# RecoveryBoard.net
KiCad netlist of a schematic drawn in EAGLE
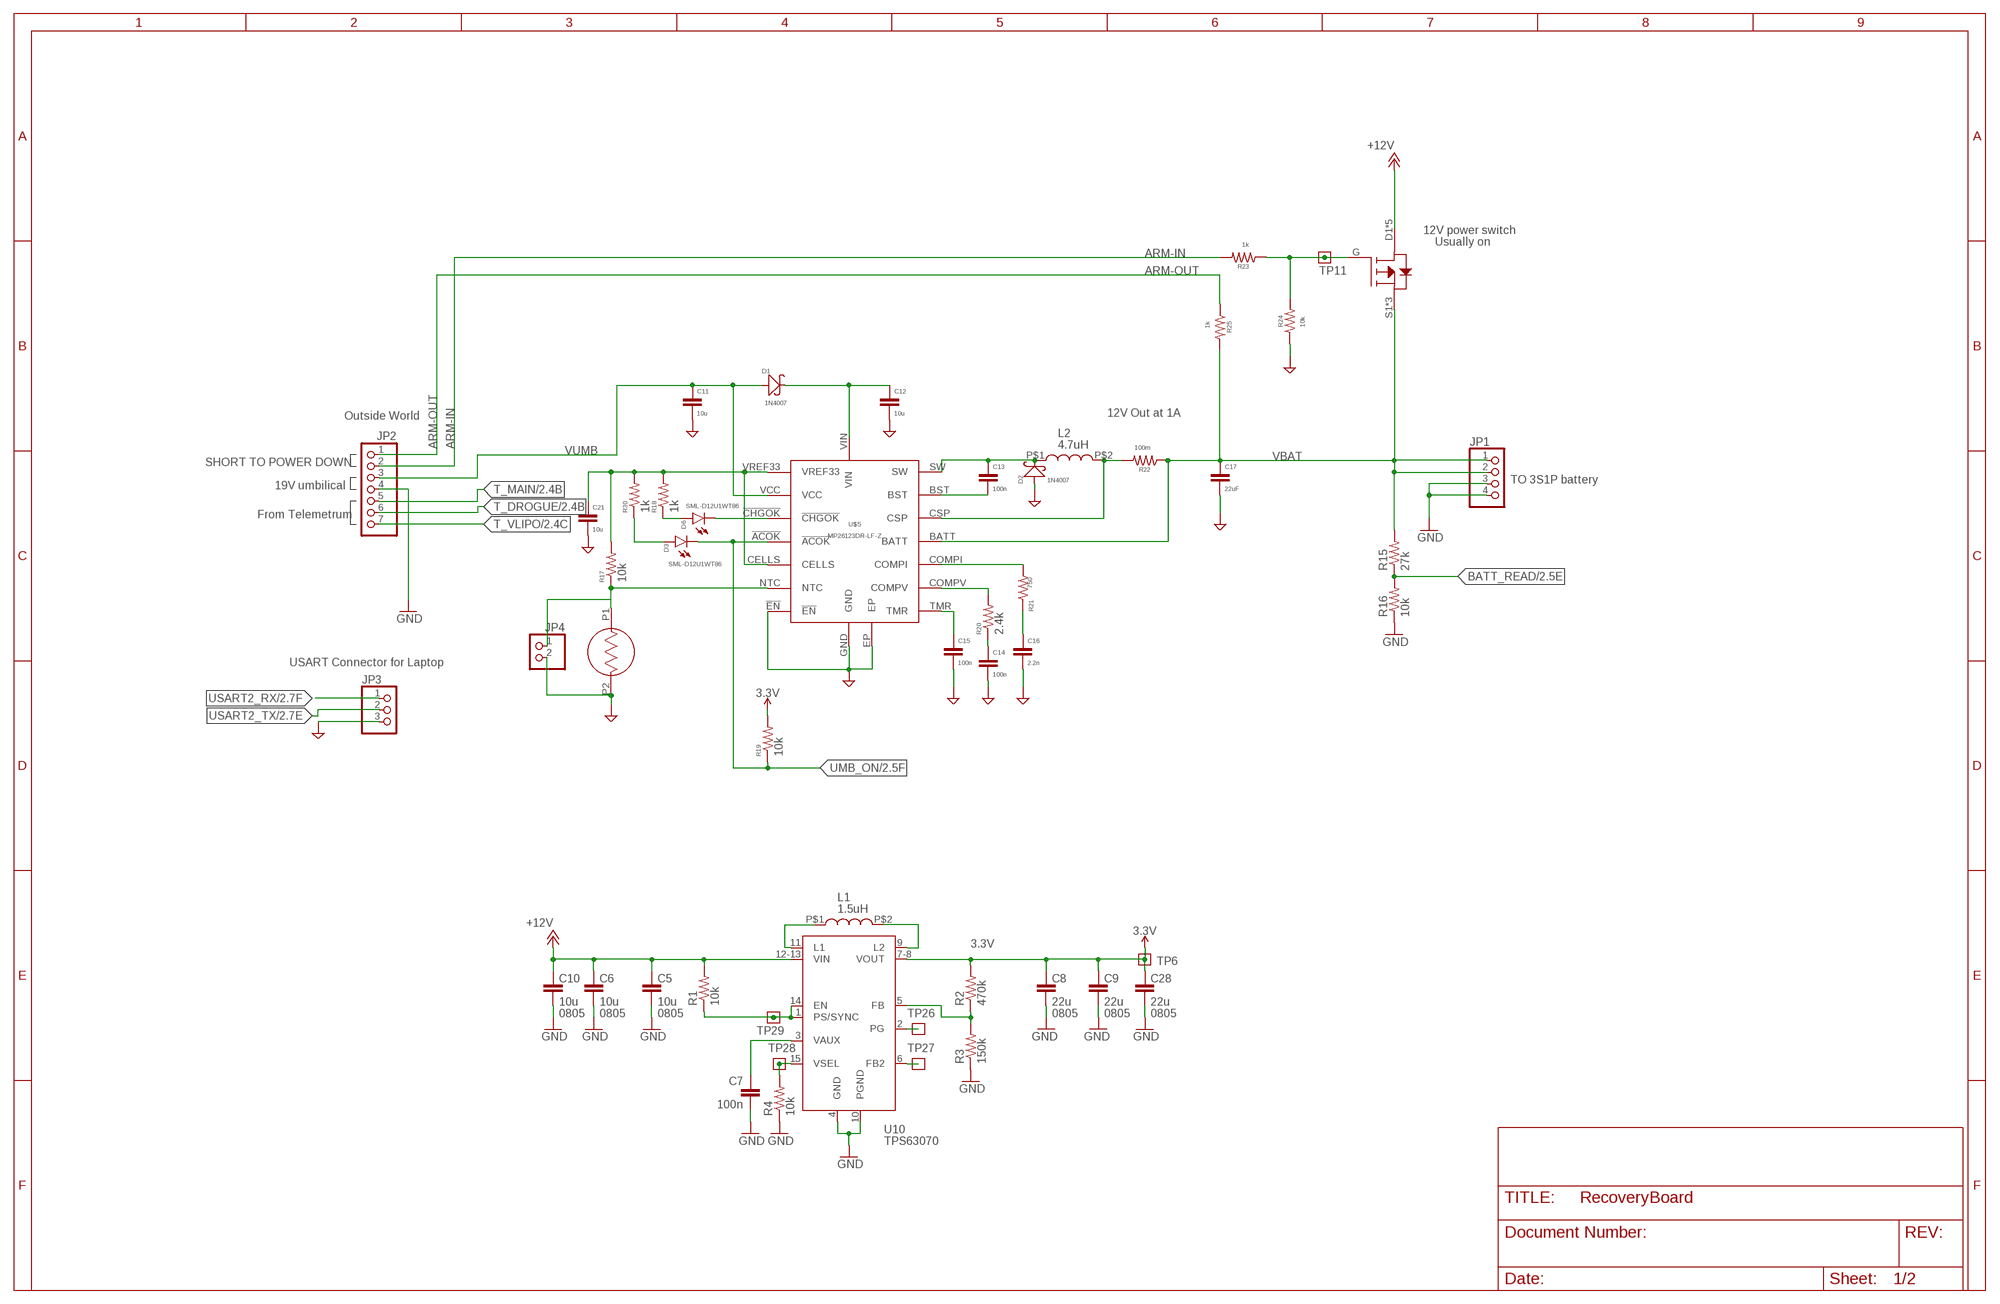
[diagram p0: schematic, sheet 1]
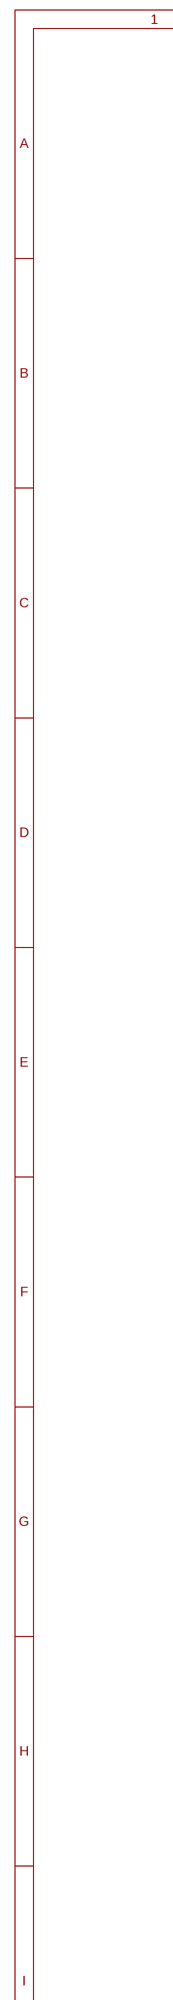
[diagram p1: schematic, sheet 2, part 1 of 2]
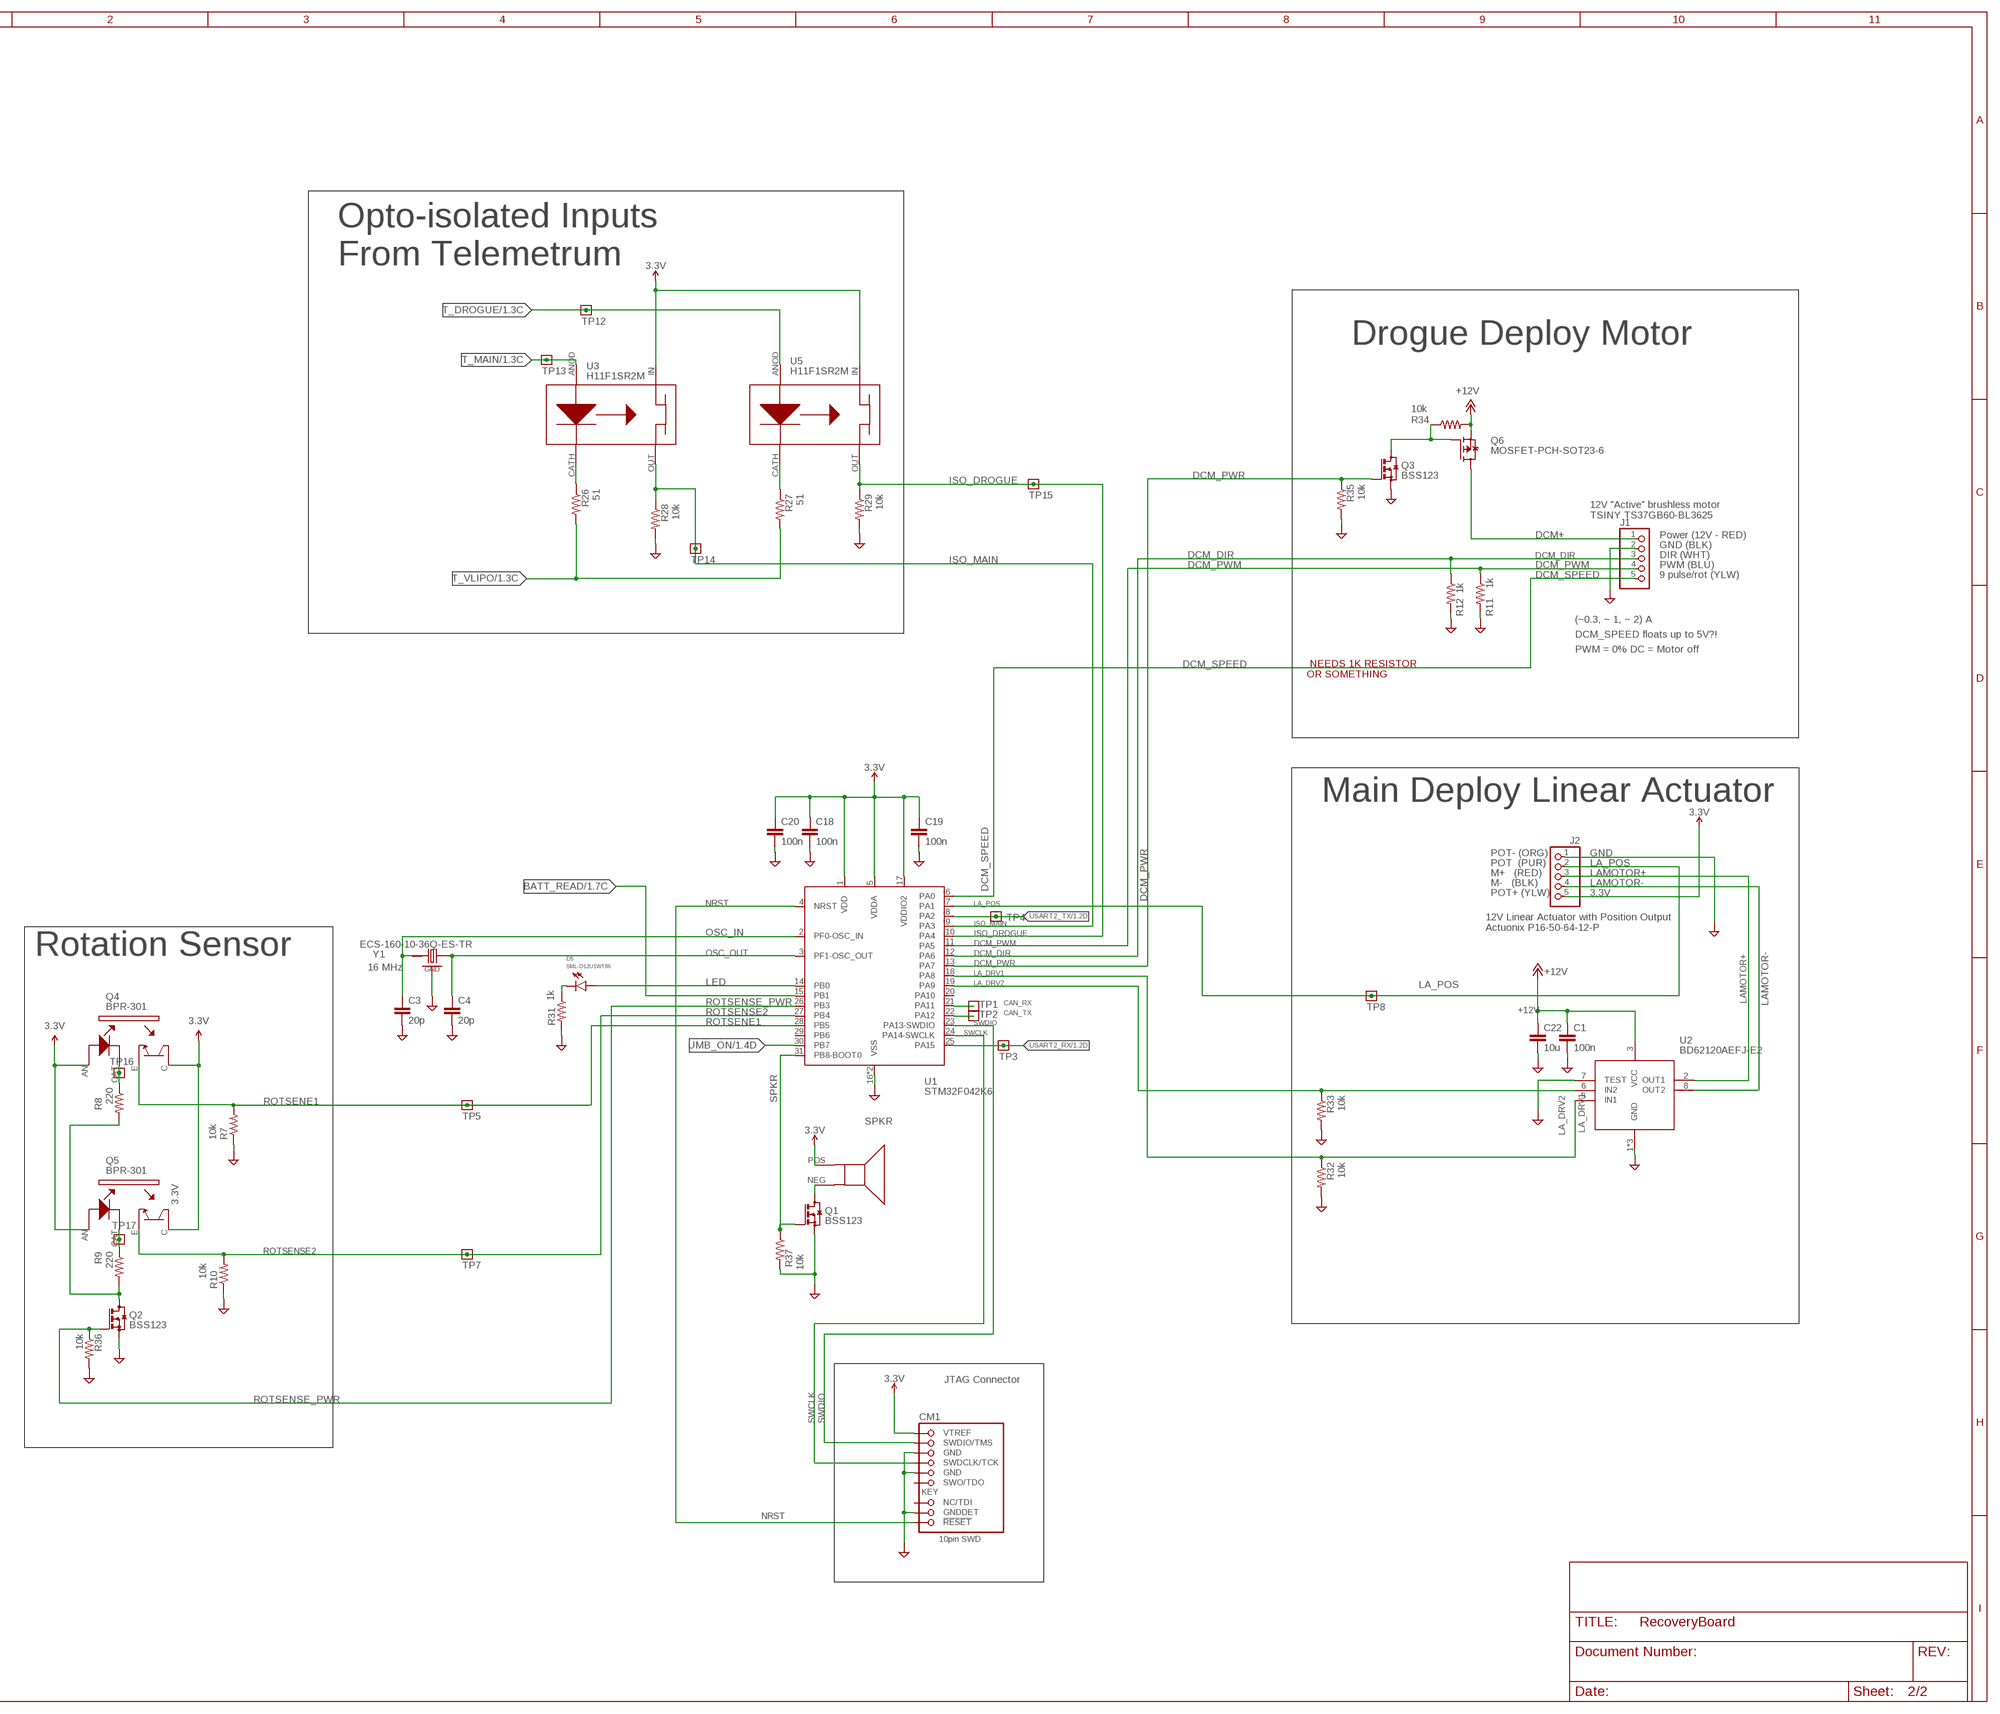
[diagram p2: schematic, sheet 2, part 2 of 2]

(export (version "E")
  (design (tool "Eeschema 10.0.6"))
  (components
    (comp (ref "C1")
      (value "100n")
      (footprint "eagle-import:.0603-C-NOSILK")
      (libsource (lib "eagle-import") (part "C-EU0603-C-NOSILK"))
    )
    (comp (ref "C3")
      (value "20p")
      (footprint "eagle-import:.0603-C-NOSILK")
      (libsource (lib "eagle-import") (part "C-EU0603-C-NOSILK"))
    )
    (comp (ref "C4")
      (value "20p")
      (footprint "eagle-import:.0603-C-NOSILK")
      (libsource (lib "eagle-import") (part "C-EU0603-C-NOSILK"))
    )
    (comp (ref "C18")
      (value "100n")
      (footprint "eagle-import:.0603-C-NOSILK")
      (libsource (lib "eagle-import") (part "C-EU0603-C-NOSILK"))
    )
    (comp (ref "C19")
      (value "100n")
      (footprint "eagle-import:.0603-C-NOSILK")
      (libsource (lib "eagle-import") (part "C-EU0603-C-NOSILK"))
    )
    (comp (ref "C20")
      (value "100n")
      (footprint "eagle-import:.0603-C-NOSILK")
      (libsource (lib "eagle-import") (part "C-EU0603-C-NOSILK"))
    )
    (comp (ref "C22")
      (value "10u")
      (footprint "eagle-import:.0805-A-NOSILK")
      (libsource (lib "eagle-import") (part "C-EU0805-A-NOSILK"))
    )
    (comp (ref "CM1")
      (value "FTSH-105-XX-X-DV-K")
      (footprint "eagle-import:CON10_2X5_DUK_FTSH")
      (libsource (lib "eagle-import") (part "FTSH-105-XX-X-DV-K"))
    )
    (comp (ref "D5")
      (value "SML-D12U1WT86")
      (footprint "eagle-import:CHIPLED_0603")
      (libsource (lib "eagle-import") (part "LEDCHIPLED_0603"))
    )
    (comp (ref "J1")
      (value "PINHD-1X5")
      (footprint "eagle-import:1X05")
      (libsource (lib "eagle-import") (part "PINHD-1X5"))
    )
    (comp (ref "J2")
      (value "PINHD-1X5")
      (footprint "eagle-import:1X05")
      (libsource (lib "eagle-import") (part "PINHD-1X5"))
    )
    (comp (ref "Q1")
      (value "BSS123")
      (footprint "eagle-import:SOT23")
      (libsource (lib "eagle-import") (part "BSS123"))
    )
    (comp (ref "Q2")
      (value "BSS123")
      (footprint "eagle-import:SOT23")
      (libsource (lib "eagle-import") (part "BSS123"))
    )
    (comp (ref "Q3")
      (value "BSS123")
      (footprint "eagle-import:SOT23")
      (libsource (lib "eagle-import") (part "BSS123"))
    )
    (comp (ref "Q4")
      (value "BPR-301")
      (footprint "eagle-import:BPR-301")
      (libsource (lib "eagle-import") (part "BPR-301"))
    )
    (comp (ref "Q5")
      (value "BPR-301")
      (footprint "eagle-import:BPR-301")
      (libsource (lib "eagle-import") (part "BPR-301"))
    )
    (comp (ref "Q6")
      (value "MOSFET-PCH-SOT23-6")
      (footprint "eagle-import:SOT23-6")
      (libsource (lib "eagle-import") (part "MOSFET-PCH-SOT23-6"))
    )
    (comp (ref "R7")
      (value "10k")
      (footprint "eagle-import:.0603-C-NOSILK")
      (libsource (lib "eagle-import") (part "R-US_0603-C-NOSILK"))
    )
    (comp (ref "R8")
      (value "220")
      (footprint "eagle-import:.0603-C-NOSILK")
      (libsource (lib "eagle-import") (part "R-US_0603-C-NOSILK"))
    )
    (comp (ref "R9")
      (value "220")
      (footprint "eagle-import:.0603-C-NOSILK")
      (libsource (lib "eagle-import") (part "R-US_0603-C-NOSILK"))
    )
    (comp (ref "R10")
      (value "10k")
      (footprint "eagle-import:.0603-C-NOSILK")
      (libsource (lib "eagle-import") (part "R-US_0603-C-NOSILK"))
    )
    (comp (ref "R11")
      (value "1k")
      (footprint "eagle-import:.0603-C-NOSILK")
      (libsource (lib "eagle-import") (part "R-US_0603-C-NOSILK"))
    )
    (comp (ref "R12")
      (value "1k")
      (footprint "eagle-import:.0603-C-NOSILK")
      (libsource (lib "eagle-import") (part "R-US_0603-C-NOSILK"))
    )
    (comp (ref "R26")
      (value "51")
      (footprint "eagle-import:.0603-C-NOSILK")
      (libsource (lib "eagle-import") (part "R-US_0603-C-NOSILK"))
    )
    (comp (ref "R27")
      (value "51")
      (footprint "eagle-import:.0603-C-NOSILK")
      (libsource (lib "eagle-import") (part "R-US_0603-C-NOSILK"))
    )
    (comp (ref "R28")
      (value "10k")
      (footprint "eagle-import:.0603-C-NOSILK")
      (libsource (lib "eagle-import") (part "R-US_0603-C-NOSILK"))
    )
    (comp (ref "R29")
      (value "10k")
      (footprint "eagle-import:.0603-C-NOSILK")
      (libsource (lib "eagle-import") (part "R-US_0603-C-NOSILK"))
    )
    (comp (ref "R31")
      (value "1k")
      (footprint "eagle-import:.0603-C-NOSILK")
      (libsource (lib "eagle-import") (part "R-US_0603-C-NOSILK"))
    )
    (comp (ref "R32")
      (value "10k")
      (footprint "eagle-import:.0603-C-NOSILK")
      (libsource (lib "eagle-import") (part "R-US_0603-C-NOSILK"))
    )
    (comp (ref "R33")
      (value "10k")
      (footprint "eagle-import:.0603-C-NOSILK")
      (libsource (lib "eagle-import") (part "R-US_0603-C-NOSILK"))
    )
    (comp (ref "R34")
      (value "10k")
      (footprint "eagle-import:.0603-C-NOSILK")
      (libsource (lib "eagle-import") (part "R-US_0603-C-NOSILK"))
    )
    (comp (ref "R35")
      (value "10k")
      (footprint "eagle-import:.0603-C-NOSILK")
      (libsource (lib "eagle-import") (part "R-US_0603-C-NOSILK"))
    )
    (comp (ref "R36")
      (value "10k")
      (footprint "eagle-import:.0603-C-NOSILK")
      (libsource (lib "eagle-import") (part "R-US_0603-C-NOSILK"))
    )
    (comp (ref "R37")
      (value "10k")
      (footprint "eagle-import:.0603-C-NOSILK")
      (libsource (lib "eagle-import") (part "R-US_0603-C-NOSILK"))
    )
    (comp (ref "TP1")
      (value "TEST-POINT")
      (footprint "eagle-import:2MM-TEST-POINT")
      (libsource (lib "eagle-import") (part "TEST-POINT"))
    )
    (comp (ref "TP2")
      (value "TEST-POINT")
      (footprint "eagle-import:2MM-TEST-POINT")
      (libsource (lib "eagle-import") (part "TEST-POINT"))
    )
    (comp (ref "TP3")
      (value "TEST-POINT")
      (footprint "eagle-import:2MM-TEST-POINT")
      (libsource (lib "eagle-import") (part "TEST-POINT"))
    )
    (comp (ref "TP4")
      (value "TEST-POINT")
      (footprint "eagle-import:2MM-TEST-POINT")
      (libsource (lib "eagle-import") (part "TEST-POINT"))
    )
    (comp (ref "TP5")
      (value "TEST-POINT")
      (footprint "eagle-import:2MM-TEST-POINT")
      (libsource (lib "eagle-import") (part "TEST-POINT"))
    )
    (comp (ref "TP7")
      (value "TEST-POINT")
      (footprint "eagle-import:2MM-TEST-POINT")
      (libsource (lib "eagle-import") (part "TEST-POINT"))
    )
    (comp (ref "TP8")
      (value "TEST-POINT")
      (footprint "eagle-import:2MM-TEST-POINT")
      (libsource (lib "eagle-import") (part "TEST-POINT"))
    )
    (comp (ref "TP12")
      (value "TEST-POINT")
      (footprint "eagle-import:2MM-TEST-POINT")
      (libsource (lib "eagle-import") (part "TEST-POINT"))
    )
    (comp (ref "TP13")
      (value "TEST-POINT")
      (footprint "eagle-import:2MM-TEST-POINT")
      (libsource (lib "eagle-import") (part "TEST-POINT"))
    )
    (comp (ref "TP14")
      (value "TEST-POINT")
      (footprint "eagle-import:2MM-TEST-POINT")
      (libsource (lib "eagle-import") (part "TEST-POINT"))
    )
    (comp (ref "TP15")
      (value "TEST-POINT")
      (footprint "eagle-import:2MM-TEST-POINT")
      (libsource (lib "eagle-import") (part "TEST-POINT"))
    )
    (comp (ref "TP16")
      (value "TEST-POINT")
      (footprint "eagle-import:2MM-TEST-POINT")
      (libsource (lib "eagle-import") (part "TEST-POINT"))
    )
    (comp (ref "TP17")
      (value "TEST-POINT")
      (footprint "eagle-import:2MM-TEST-POINT")
      (libsource (lib "eagle-import") (part "TEST-POINT"))
    )
    (comp (ref "U$7")
      (value "SMT-0440-S-R")
      (footprint "eagle-import:SMT-0440-S-R")
      (libsource (lib "eagle-import") (part "SMT-0440-S-R"))
    )
    (comp (ref "U1")
      (value "STM32F042K6")
      (footprint "eagle-import:QFP32-7X7")
      (libsource (lib "eagle-import") (part "STM32F042K6"))
    )
    (comp (ref "U2")
      (value "BD62120AEFJ-E2")
      (footprint "eagle-import:SOIC127P600X100-9N")
      (fields (field (name "MOUSER_PART_NUMBER") "755-BD62120AEFJ-E2"))
      (libsource (lib "eagle-import") (part "BD62120AEFJ-E2"))
    )
    (comp (ref "U3")
      (value "H11F1SR2M")
      (footprint "eagle-import:H11F1SR2M")
      (libsource (lib "eagle-import") (part "H11F1SR2M"))
    )
    (comp (ref "U5")
      (value "H11F1SR2M")
      (footprint "eagle-import:H11F1SR2M")
      (libsource (lib "eagle-import") (part "H11F1SR2M"))
    )
    (comp (ref "Y1")
      (value "ECS-160-10-36Q-ES-TR")
      (footprint "eagle-import:XTAL_ECS-160-10-36Q-ES-TR")
      (fields (field (name "DIGI-KEY_PART_NUMBER") "XC2181CT-ND") (field (name "MF") "ECS Inc."))
      (libsource (lib "eagle-import") (part "ECS-160-10-36Q-ES-TR"))
    )
    (comp (ref "C5")
      (value "10u")
      (footprint "eagle-import:.0805-C-NOSILK")
      (fields (field (name "MFR") "Samsung") (field (name "MPN") "CL05B104KO5NNNC"))
      (libsource (lib "eagle-import") (part "C-EU0805-C-NOSILK"))
    )
    (comp (ref "C6")
      (value "10u")
      (footprint "eagle-import:.0805-C-NOSILK")
      (libsource (lib "eagle-import") (part "C-EU0805-C-NOSILK"))
    )
    (comp (ref "C7")
      (value "100n")
      (footprint "eagle-import:.0603-C-NOSILK")
      (fields (field (name "MFR") "Samsung") (field (name "MPN") "CL05B104KO5NNNC"))
      (libsource (lib "eagle-import") (part "C-EU0603-C-NOSILK"))
    )
    (comp (ref "C8")
      (value "22u")
      (footprint "eagle-import:.0805-C-NOSILK")
      (fields (field (name "MFR") "Samsung") (field (name "MPN") "CL05B104KO5NNNC"))
      (libsource (lib "eagle-import") (part "C-EU0805-C-NOSILK"))
    )
    (comp (ref "C9")
      (value "22u")
      (footprint "eagle-import:.0805-C-NOSILK")
      (libsource (lib "eagle-import") (part "C-EU0805-C-NOSILK"))
    )
    (comp (ref "C10")
      (value "10u")
      (footprint "eagle-import:.0805-C-NOSILK")
      (libsource (lib "eagle-import") (part "C-EU0805-C-NOSILK"))
    )
    (comp (ref "C11")
      (value "10u")
      (footprint "eagle-import:.0805-C-NOSILK")
      (libsource (lib "eagle-import") (part "C-EU0805-C-NOSILK"))
    )
    (comp (ref "C12")
      (value "10u")
      (footprint "eagle-import:.0805-C-NOSILK")
      (libsource (lib "eagle-import") (part "C-EU0805-C-NOSILK"))
    )
    (comp (ref "C13")
      (value "100n")
      (footprint "eagle-import:.0603-C-NOSILK")
      (libsource (lib "eagle-import") (part "C-EU0603-C-NOSILK"))
    )
    (comp (ref "C14")
      (value "100n")
      (footprint "eagle-import:.0603-C-NOSILK")
      (libsource (lib "eagle-import") (part "C-EU0603-C-NOSILK"))
    )
    (comp (ref "C15")
      (value "100n")
      (footprint "eagle-import:.0603-C-NOSILK")
      (libsource (lib "eagle-import") (part "C-EU0603-C-NOSILK"))
    )
    (comp (ref "C16")
      (value "2.2n")
      (footprint "eagle-import:.0603-C-NOSILK")
      (libsource (lib "eagle-import") (part "C-EU0603-C-NOSILK"))
    )
    (comp (ref "C17")
      (value "22uF")
      (footprint "eagle-import:.0805-C-NOSILK")
      (libsource (lib "eagle-import") (part "C-EU0805-C-NOSILK"))
    )
    (comp (ref "C21")
      (value "10u")
      (footprint "eagle-import:.0805-C-NOSILK")
      (libsource (lib "eagle-import") (part "C-EU0805-C-NOSILK"))
    )
    (comp (ref "C28")
      (value "22u")
      (footprint "eagle-import:.0805-C-NOSILK")
      (libsource (lib "eagle-import") (part "C-EU0805-C-NOSILK"))
    )
    (comp (ref "D1")
      (value "1N4007")
      (footprint "eagle-import:DO-214AC")
      (libsource (lib "eagle-import") (part "DIODE-SCHOTTKY-(DO-214AC)"))
    )
    (comp (ref "D2")
      (value "1N4007")
      (footprint "eagle-import:DO-214AC")
      (libsource (lib "eagle-import") (part "DIODE-SCHOTTKY-(DO-214AC)"))
    )
    (comp (ref "D3")
      (value "SML-D12U1WT86")
      (footprint "eagle-import:CHIPLED_0603")
      (libsource (lib "eagle-import") (part "LEDCHIPLED_0603"))
    )
    (comp (ref "D6")
      (value "SML-D12U1WT86")
      (footprint "eagle-import:CHIPLED_0603")
      (libsource (lib "eagle-import") (part "LEDCHIPLED_0603"))
    )
    (comp (ref "JP1")
      (value "PINHD-1X4")
      (footprint "eagle-import:1X04")
      (libsource (lib "eagle-import") (part "PINHD-1X4"))
    )
    (comp (ref "JP2")
      (value "PINHD-1X7")
      (footprint "eagle-import:1X07")
      (libsource (lib "eagle-import") (part "PINHD-1X7"))
    )
    (comp (ref "JP3")
      (value "PINHD-1X3")
      (footprint "eagle-import:1X03")
      (libsource (lib "eagle-import") (part "PINHD-1X3"))
    )
    (comp (ref "JP4")
      (value "PINHD-1X2")
      (footprint "eagle-import:1X02")
      (libsource (lib "eagle-import") (part "PINHD-1X2"))
    )
    (comp (ref "L1")
      (value "1.5uH")
      (footprint "eagle-import:IHLP2020CZER1R5M11")
      (fields (field (name "MFR") "Vishay Dale") (field (name "MPN") "IHLP2020BZER4R7M11"))
      (libsource (lib "eagle-import") (part "IHLP2020CZER1R5M11"))
    )
    (comp (ref "L2")
      (value "4.7uH")
      (footprint "eagle-import:IHLP2020BZER4R7M11")
      (fields (field (name "MFR") "Vishay Dale") (field (name "MPN") "IHLP2020BZER4R7M11"))
      (libsource (lib "eagle-import") (part "IHLP2020BZER4R7M11"))
    )
    (comp (ref "Q7")
      (value "SI7465DP-T1-E3")
      (footprint "eagle-import:SI7465DP-T1-E3CT-ND")
      (fields (field (name "MFR") "Vishay Siliconix"))
      (libsource (lib "eagle-import") (part "SI7465DP-T1-E3"))
    )
    (comp (ref "R1")
      (value "10k")
      (footprint "eagle-import:.0603-C-NOSILK")
      (fields (field (name "MFR") "Samsung") (field (name "MPN") "RC1005F6653CS"))
      (libsource (lib "eagle-import") (part "R-US_0603-C-NOSILK"))
    )
    (comp (ref "R2")
      (value "470k")
      (footprint "eagle-import:.0603-C-NOSILK")
      (fields (field (name "MFR") "Samsung") (field (name "MPN") "RC1005F6653CS"))
      (libsource (lib "eagle-import") (part "R-US_0603-C-NOSILK"))
    )
    (comp (ref "R3")
      (value "150k")
      (footprint "eagle-import:.0603-C-NOSILK")
      (fields (field (name "MFR") "Samsung") (field (name "MPN") "RC1005F6653CS"))
      (libsource (lib "eagle-import") (part "R-US_0603-C-NOSILK"))
    )
    (comp (ref "R4")
      (value "10k")
      (footprint "eagle-import:.0603-C-NOSILK")
      (fields (field (name "MFR") "Samsung") (field (name "MPN") "RC1005F6653CS"))
      (libsource (lib "eagle-import") (part "R-US_0603-C-NOSILK"))
    )
    (comp (ref "R5")
      (value "NHQ103B375T10")
      (footprint "eagle-import:NHQ103B375T10")
      (libsource (lib "eagle-import") (part "NHQ103B375T10"))
    )
    (comp (ref "R15")
      (value "27k")
      (footprint "eagle-import:.0603-C-NOSILK")
      (fields (field (name "MFR") "Samsung") (field (name "MPN") "RC1005F6653CS"))
      (libsource (lib "eagle-import") (part "R-US_0603-C-NOSILK"))
    )
    (comp (ref "R16")
      (value "10k")
      (footprint "eagle-import:.0603-C-NOSILK")
      (fields (field (name "MFR") "Samsung") (field (name "MPN") "RC1005F6653CS"))
      (libsource (lib "eagle-import") (part "R-US_0603-C-NOSILK"))
    )
    (comp (ref "R17")
      (value "10k")
      (footprint "eagle-import:.0603-C-NOSILK")
      (libsource (lib "eagle-import") (part "R-US_0603-C-NOSILK"))
    )
    (comp (ref "R18")
      (value "1k")
      (footprint "eagle-import:.0603-C-NOSILK")
      (libsource (lib "eagle-import") (part "R-US_0603-C-NOSILK"))
    )
    (comp (ref "R19")
      (value "10k")
      (footprint "eagle-import:.0603-C-NOSILK")
      (libsource (lib "eagle-import") (part "R-US_0603-C-NOSILK"))
    )
    (comp (ref "R20")
      (value "2.4k")
      (footprint "eagle-import:.0603-C-NOSILK")
      (libsource (lib "eagle-import") (part "R-US_0603-C-NOSILK"))
    )
    (comp (ref "R21")
      (value "750")
      (footprint "eagle-import:.0603-C-NOSILK")
      (libsource (lib "eagle-import") (part "R-US_0603-C-NOSILK"))
    )
    (comp (ref "R22")
      (value "100m")
      (footprint "eagle-import:1206-C")
      (libsource (lib "eagle-import") (part "R-US_1206-C"))
    )
    (comp (ref "R23")
      (value "1k")
      (footprint "eagle-import:.0603-C-NOSILK")
      (libsource (lib "eagle-import") (part "R-US_0603-C-NOSILK"))
    )
    (comp (ref "R24")
      (value "10k")
      (footprint "eagle-import:.0603-C-NOSILK")
      (libsource (lib "eagle-import") (part "R-US_0603-C-NOSILK"))
    )
    (comp (ref "R25")
      (value "1k")
      (footprint "eagle-import:.0603-C-NOSILK")
      (libsource (lib "eagle-import") (part "R-US_0603-C-NOSILK"))
    )
    (comp (ref "R30")
      (value "1k")
      (footprint "eagle-import:.0603-C-NOSILK")
      (libsource (lib "eagle-import") (part "R-US_0603-C-NOSILK"))
    )
    (comp (ref "TP6")
      (value "TEST-POINT")
      (footprint "eagle-import:2MM-TEST-POINT")
      (libsource (lib "eagle-import") (part "TEST-POINT"))
    )
    (comp (ref "TP11")
      (value "TEST-POINT")
      (footprint "eagle-import:2MM-TEST-POINT")
      (libsource (lib "eagle-import") (part "TEST-POINT"))
    )
    (comp (ref "TP26")
      (value "TEST-POINT")
      (footprint "eagle-import:2MM-TEST-POINT")
      (libsource (lib "eagle-import") (part "TEST-POINT"))
    )
    (comp (ref "TP27")
      (value "TEST-POINT")
      (footprint "eagle-import:2MM-TEST-POINT")
      (libsource (lib "eagle-import") (part "TEST-POINT"))
    )
    (comp (ref "TP28")
      (value "TEST-POINT")
      (footprint "eagle-import:2MM-TEST-POINT")
      (libsource (lib "eagle-import") (part "TEST-POINT"))
    )
    (comp (ref "TP29")
      (value "TEST-POINT")
      (footprint "eagle-import:2MM-TEST-POINT")
      (libsource (lib "eagle-import") (part "TEST-POINT"))
    )
    (comp (ref "U$5")
      (value "MP26123DR-LF-Z")
      (footprint "eagle-import:MP26123DR-LF-Z")
      (libsource (lib "eagle-import") (part "MP26123DR-LF-Z"))
    )
    (comp (ref "U10")
      (value "TPS63070")
      (footprint "eagle-import:TPS63070X")
      (libsource (lib "eagle-import") (part "TPS63070X"))
    )
  )
  (nets
    (net (code "1") (name "+12V") (class "Default")
      (node (ref "C1") (pin "1") (pinfunction "1_1") (pintype "passive"))
      (node (ref "C10") (pin "1") (pinfunction "1_1") (pintype "passive"))
      (node (ref "C22") (pin "1") (pinfunction "1_1") (pintype "passive"))
      (node (ref "C5") (pin "1") (pinfunction "1_1") (pintype "passive"))
      (node (ref "C6") (pin "1") (pinfunction "1_1") (pintype "passive"))
      (node (ref "Q6") (pin "4") (pinfunction "S_4") (pintype "passive"))
      (node (ref "Q7") (pin "D1") (pinfunction "D_D1") (pintype "bidirectional"))
      (node (ref "Q7") (pin "D2") (pinfunction "D_D2") (pintype "bidirectional"))
      (node (ref "Q7") (pin "D3") (pinfunction "D_D3") (pintype "bidirectional"))
      (node (ref "Q7") (pin "D4") (pinfunction "D_D4") (pintype "bidirectional"))
      (node (ref "Q7") (pin "DPAD") (pinfunction "D_DPAD") (pintype "bidirectional"))
      (node (ref "R1") (pin "2") (pinfunction "2_2") (pintype "passive"))
      (node (ref "R34") (pin "2") (pinfunction "2_2") (pintype "passive"))
      (node (ref "U10") (pin "12-13") (pinfunction "VIN_12-13") (pintype "power_in"))
      (node (ref "U2") (pin "3") (pinfunction "VCC_3") (pintype "bidirectional"))
    )
    (net (code "2") (name "3.3V") (class "Default")
      (node (ref "C18") (pin "1") (pinfunction "1_1") (pintype "passive"))
      (node (ref "C19") (pin "1") (pinfunction "1_1") (pintype "passive"))
      (node (ref "C20") (pin "1") (pinfunction "1_1") (pintype "passive"))
      (node (ref "C28") (pin "1") (pinfunction "1_1") (pintype "passive"))
      (node (ref "C8") (pin "1") (pinfunction "1_1") (pintype "passive"))
      (node (ref "C9") (pin "1") (pinfunction "1_1") (pintype "passive"))
      (node (ref "CM1") (pin "1") (pinfunction "VTREF_1") (pintype "passive"))
      (node (ref "J2") (pin "5") (pinfunction "5_5") (pintype "passive"))
      (node (ref "Q4") (pin "AN") (pinfunction "ANOD_AN") (pintype "bidirectional"))
      (node (ref "Q4") (pin "C") (pinfunction "COLL_C") (pintype "bidirectional"))
      (node (ref "Q5") (pin "AN") (pinfunction "ANOD_AN") (pintype "bidirectional"))
      (node (ref "Q5") (pin "C") (pinfunction "COLL_C") (pintype "bidirectional"))
      (node (ref "R19") (pin "2") (pinfunction "2_2") (pintype "passive"))
      (node (ref "R2") (pin "2") (pinfunction "2_2") (pintype "passive"))
      (node (ref "TP6") (pin "1") (pinfunction "1_1") (pintype "passive"))
      (node (ref "U$7") (pin "POS") (pinfunction "POS_POS") (pintype "bidirectional"))
      (node (ref "U1") (pin "1") (pinfunction "VDD_1") (pintype "power_in"))
      (node (ref "U1") (pin "17") (pinfunction "VDDIO2_17") (pintype "power_in"))
      (node (ref "U1") (pin "5") (pinfunction "VDDA_5") (pintype "power_in"))
      (node (ref "U10") (pin "7-8") (pinfunction "VOUT_7-8") (pintype "power_in"))
      (node (ref "U3") (pin "IN") (pinfunction "IN_IN") (pintype "bidirectional"))
      (node (ref "U5") (pin "IN") (pinfunction "IN_IN") (pintype "bidirectional"))
    )
    (net (code "3") (name "ARM-IN") (class "Default")
      (node (ref "JP2") (pin "2") (pinfunction "2_2") (pintype "passive"))
      (node (ref "R23") (pin "2") (pinfunction "2_2") (pintype "passive"))
    )
    (net (code "4") (name "ARM-OUT") (class "Default")
      (node (ref "JP2") (pin "1") (pinfunction "1_1") (pintype "passive"))
      (node (ref "R25") (pin "1") (pinfunction "1_1") (pintype "passive"))
    )
    (net (code "5") (name "BATT_READ") (class "Default")
      (node (ref "R15") (pin "1") (pinfunction "1_1") (pintype "passive"))
      (node (ref "R16") (pin "2") (pinfunction "2_2") (pintype "passive"))
      (node (ref "U1") (pin "15") (pinfunction "PB1_15") (pintype "bidirectional"))
    )
    (net (code "6") (name "CAN_RX") (class "Default")
      (node (ref "TP1") (pin "1") (pinfunction "1_1") (pintype "passive"))
      (node (ref "U1") (pin "21") (pinfunction "PA11_21") (pintype "bidirectional"))
    )
    (net (code "7") (name "CAN_TX") (class "Default")
      (node (ref "TP2") (pin "1") (pinfunction "1_1") (pintype "passive"))
      (node (ref "U1") (pin "22") (pinfunction "PA12_22") (pintype "bidirectional"))
    )
    (net (code "8") (name "DCM+") (class "Default")
      (node (ref "J1") (pin "1") (pinfunction "1_1") (pintype "passive"))
      (node (ref "Q6") (pin "1") (pinfunction "D_1") (pintype "passive"))
      (node (ref "Q6") (pin "2") (pinfunction "D_2") (pintype "passive"))
      (node (ref "Q6") (pin "5") (pinfunction "D_5") (pintype "passive"))
      (node (ref "Q6") (pin "6") (pinfunction "D_6") (pintype "passive"))
    )
    (net (code "9") (name "DCM_DIR") (class "Default")
      (node (ref "J1") (pin "3") (pinfunction "3_3") (pintype "passive"))
      (node (ref "R12") (pin "1") (pinfunction "1_1") (pintype "passive"))
      (node (ref "U1") (pin "12") (pinfunction "PA6_12") (pintype "bidirectional"))
    )
    (net (code "10") (name "DCM_PWM") (class "Default")
      (node (ref "J1") (pin "4") (pinfunction "4_4") (pintype "passive"))
      (node (ref "R11") (pin "1") (pinfunction "1_1") (pintype "passive"))
      (node (ref "U1") (pin "11") (pinfunction "PA5_11") (pintype "bidirectional"))
    )
    (net (code "11") (name "DCM_PWR") (class "Default")
      (node (ref "Q3") (pin "1") (pinfunction "G_1") (pintype "passive"))
      (node (ref "R35") (pin "1") (pinfunction "1_1") (pintype "passive"))
      (node (ref "U1") (pin "13") (pinfunction "PA7_13") (pintype "bidirectional"))
    )
    (net (code "12") (name "DCM_SPEED") (class "Default")
      (node (ref "J1") (pin "5") (pinfunction "5_5") (pintype "passive"))
      (node (ref "U1") (pin "6") (pinfunction "PA0_6") (pintype "bidirectional"))
    )
    (net (code "13") (name "GND") (class "Default")
      (node (ref "C1") (pin "2") (pinfunction "2_2") (pintype "passive"))
      (node (ref "C10") (pin "2") (pinfunction "2_2") (pintype "passive"))
      (node (ref "C11") (pin "2") (pinfunction "2_2") (pintype "passive"))
      (node (ref "C12") (pin "2") (pinfunction "2_2") (pintype "passive"))
      (node (ref "C14") (pin "2") (pinfunction "2_2") (pintype "passive"))
      (node (ref "C15") (pin "2") (pinfunction "2_2") (pintype "passive"))
      (node (ref "C16") (pin "2") (pinfunction "2_2") (pintype "passive"))
      (node (ref "C17") (pin "2") (pinfunction "2_2") (pintype "passive"))
      (node (ref "C18") (pin "2") (pinfunction "2_2") (pintype "passive"))
      (node (ref "C19") (pin "2") (pinfunction "2_2") (pintype "passive"))
      (node (ref "C20") (pin "2") (pinfunction "2_2") (pintype "passive"))
      (node (ref "C21") (pin "2") (pinfunction "2_2") (pintype "passive"))
      (node (ref "C22") (pin "2") (pinfunction "2_2") (pintype "passive"))
      (node (ref "C28") (pin "2") (pinfunction "2_2") (pintype "passive"))
      (node (ref "C3") (pin "2") (pinfunction "2_2") (pintype "passive"))
      (node (ref "C4") (pin "2") (pinfunction "2_2") (pintype "passive"))
      (node (ref "C5") (pin "2") (pinfunction "2_2") (pintype "passive"))
      (node (ref "C6") (pin "2") (pinfunction "2_2") (pintype "passive"))
      (node (ref "C7") (pin "2") (pinfunction "2_2") (pintype "passive"))
      (node (ref "C8") (pin "2") (pinfunction "2_2") (pintype "passive"))
      (node (ref "C9") (pin "2") (pinfunction "2_2") (pintype "passive"))
      (node (ref "CM1") (pin "3") (pinfunction "GND_3") (pintype "passive"))
      (node (ref "CM1") (pin "5") (pinfunction "GND_5") (pintype "passive"))
      (node (ref "CM1") (pin "9") (pinfunction "GNDDET_9") (pintype "passive"))
      (node (ref "D2") (pin "1") (pinfunction "+_1") (pintype "passive"))
      (node (ref "J1") (pin "2") (pinfunction "2_2") (pintype "passive"))
      (node (ref "J2") (pin "1") (pinfunction "1_1") (pintype "passive"))
      (node (ref "JP1") (pin "3") (pinfunction "3_3") (pintype "passive"))
      (node (ref "JP1") (pin "4") (pinfunction "4_4") (pintype "passive"))
      (node (ref "JP2") (pin "4") (pinfunction "4_4") (pintype "passive"))
      (node (ref "JP3") (pin "3") (pinfunction "3_3") (pintype "passive"))
      (node (ref "JP4") (pin "2") (pinfunction "2_2") (pintype "passive"))
      (node (ref "Q1") (pin "2") (pinfunction "S_2") (pintype "passive"))
      (node (ref "Q2") (pin "2") (pinfunction "S_2") (pintype "passive"))
      (node (ref "Q3") (pin "2") (pinfunction "S_2") (pintype "passive"))
      (node (ref "R10") (pin "1") (pinfunction "1_1") (pintype "passive"))
      (node (ref "R11") (pin "2") (pinfunction "2_2") (pintype "passive"))
      (node (ref "R12") (pin "2") (pinfunction "2_2") (pintype "passive"))
      (node (ref "R16") (pin "1") (pinfunction "1_1") (pintype "passive"))
      (node (ref "R24") (pin "1") (pinfunction "1_1") (pintype "passive"))
      (node (ref "R28") (pin "2") (pinfunction "2_2") (pintype "passive"))
      (node (ref "R29") (pin "2") (pinfunction "2_2") (pintype "passive"))
      (node (ref "R3") (pin "1") (pinfunction "1_1") (pintype "passive"))
      (node (ref "R31") (pin "2") (pinfunction "2_2") (pintype "passive"))
      (node (ref "R32") (pin "2") (pinfunction "2_2") (pintype "passive"))
      (node (ref "R33") (pin "2") (pinfunction "2_2") (pintype "passive"))
      (node (ref "R35") (pin "2") (pinfunction "2_2") (pintype "passive"))
      (node (ref "R36") (pin "2") (pinfunction "2_2") (pintype "passive"))
      (node (ref "R37") (pin "2") (pinfunction "2_2") (pintype "passive"))
      (node (ref "R4") (pin "1") (pinfunction "1_1") (pintype "passive"))
      (node (ref "R5") (pin "P2") (pinfunction "P$2_P2") (pintype "bidirectional"))
      (node (ref "R7") (pin "1") (pinfunction "1_1") (pintype "passive"))
      (node (ref "U$5") (pin "!EN") (pinfunction "~{EN}_!EN") (pintype "bidirectional"))
      (node (ref "U$5") (pin "EP") (pinfunction "EP_EP") (pintype "bidirectional"))
      (node (ref "U$5") (pin "GND") (pinfunction "GND_GND") (pintype "bidirectional"))
      (node (ref "U1") (pin "16") (pinfunction "VSS_16") (pintype "power_in"))
      (node (ref "U1") (pin "32") (pinfunction "VSS_32") (pintype "power_in"))
      (node (ref "U10") (pin "10") (pinfunction "PGND_10") (pintype "power_in"))
      (node (ref "U10") (pin "4") (pinfunction "GND_4") (pintype "power_in"))
      (node (ref "U2") (pin "1") (pinfunction "GND_1") (pintype "bidirectional"))
      (node (ref "U2") (pin "4") (pinfunction "GND_4") (pintype "bidirectional"))
      (node (ref "U2") (pin "7") (pinfunction "TEST_7") (pintype "bidirectional"))
      (node (ref "U2") (pin "9") (pinfunction "GND_9") (pintype "bidirectional"))
      (node (ref "Y1") (pin "GND") (pinfunction "GND_GND") (pintype "power_in"))
      (node (ref "Y1") (pin "GND2") (pinfunction "GND_GND2") (pintype "power_in"))
    )
    (net (code "14") (name "ISO_DROGUE") (class "Default")
      (node (ref "R29") (pin "1") (pinfunction "1_1") (pintype "passive"))
      (node (ref "TP15") (pin "1") (pinfunction "1_1") (pintype "passive"))
      (node (ref "U1") (pin "10") (pinfunction "PA4_10") (pintype "bidirectional"))
      (node (ref "U5") (pin "OUT") (pinfunction "OUT_OUT") (pintype "bidirectional"))
    )
    (net (code "15") (name "ISO_MAIN") (class "Default")
      (node (ref "R28") (pin "1") (pinfunction "1_1") (pintype "passive"))
      (node (ref "TP14") (pin "1") (pinfunction "1_1") (pintype "passive"))
      (node (ref "U1") (pin "9") (pinfunction "PA3_9") (pintype "bidirectional"))
      (node (ref "U3") (pin "OUT") (pinfunction "OUT_OUT") (pintype "bidirectional"))
    )
    (net (code "16") (name "LAMOTOR+") (class "Default")
      (node (ref "J2") (pin "3") (pinfunction "3_3") (pintype "passive"))
      (node (ref "U2") (pin "2") (pinfunction "OUT1_2") (pintype "bidirectional"))
    )
    (net (code "17") (name "LAMOTOR-") (class "Default")
      (node (ref "J2") (pin "4") (pinfunction "4_4") (pintype "passive"))
      (node (ref "U2") (pin "8") (pinfunction "OUT2_8") (pintype "bidirectional"))
    )
    (net (code "18") (name "LA_DRV1") (class "Default")
      (node (ref "R32") (pin "1") (pinfunction "1_1") (pintype "passive"))
      (node (ref "U1") (pin "18") (pinfunction "PA8_18") (pintype "bidirectional"))
      (node (ref "U2") (pin "5") (pinfunction "IN1_5") (pintype "bidirectional"))
    )
    (net (code "19") (name "LA_DRV2") (class "Default")
      (node (ref "R33") (pin "1") (pinfunction "1_1") (pintype "passive"))
      (node (ref "U1") (pin "19") (pinfunction "PA9_19") (pintype "bidirectional"))
      (node (ref "U2") (pin "6") (pinfunction "IN2_6") (pintype "bidirectional"))
    )
    (net (code "20") (name "LA_POS") (class "Default")
      (node (ref "J2") (pin "2") (pinfunction "2_2") (pintype "passive"))
      (node (ref "TP8") (pin "1") (pinfunction "1_1") (pintype "passive"))
      (node (ref "U1") (pin "7") (pinfunction "PA1_7") (pintype "bidirectional"))
    )
    (net (code "21") (name "LED") (class "Default")
      (node (ref "D5") (pin "A") (pinfunction "A_A") (pintype "passive"))
      (node (ref "U1") (pin "14") (pinfunction "PB0_14") (pintype "bidirectional"))
    )
    (net (code "22") (name "NRST") (class "Default")
      (node (ref "CM1") (pin "10") (pinfunction "~{RESET}_10") (pintype "passive"))
      (node (ref "U1") (pin "4") (pinfunction "NRST_4") (pintype "bidirectional"))
    )
    (net (code "23") (name "Net-(C13-Pad2)") (class "Default")
      (node (ref "C13") (pin "2") (pinfunction "2_2") (pintype "passive"))
      (node (ref "U$5") (pin "BST") (pinfunction "BST_BST") (pintype "bidirectional"))
    )
    (net (code "24") (name "Net-(C14-Pad1)") (class "Default")
      (node (ref "C14") (pin "1") (pinfunction "1_1") (pintype "passive"))
      (node (ref "R20") (pin "1") (pinfunction "1_1") (pintype "passive"))
    )
    (net (code "25") (name "Net-(C15-Pad1)") (class "Default")
      (node (ref "C15") (pin "1") (pinfunction "1_1") (pintype "passive"))
      (node (ref "U$5") (pin "TMR") (pinfunction "TMR_TMR") (pintype "bidirectional"))
    )
    (net (code "26") (name "Net-(C16-Pad1)") (class "Default")
      (node (ref "C16") (pin "1") (pinfunction "1_1") (pintype "passive"))
      (node (ref "R21") (pin "1") (pinfunction "1_1") (pintype "passive"))
    )
    (net (code "27") (name "Net-(C21-Pad1)") (class "Default")
      (node (ref "C21") (pin "1") (pinfunction "1_1") (pintype "passive"))
      (node (ref "R17") (pin "2") (pinfunction "2_2") (pintype "passive"))
      (node (ref "R18") (pin "2") (pinfunction "2_2") (pintype "passive"))
      (node (ref "R30") (pin "2") (pinfunction "2_2") (pintype "passive"))
      (node (ref "U$5") (pin "CELLS") (pinfunction "CELLS_CELLS") (pintype "bidirectional"))
      (node (ref "U$5") (pin "VREF33") (pinfunction "VREF33_VREF33") (pintype "bidirectional"))
    )
    (net (code "28") (name "Net-(D1--)") (class "Default")
      (node (ref "C12") (pin "1") (pinfunction "1_1") (pintype "passive"))
      (node (ref "D1") (pin "2") (pinfunction "-_2") (pintype "passive"))
      (node (ref "U$5") (pin "VIN") (pinfunction "VIN_VIN") (pintype "bidirectional"))
    )
    (net (code "29") (name "Net-(D2--)") (class "Default")
      (node (ref "C13") (pin "1") (pinfunction "1_1") (pintype "passive"))
      (node (ref "D2") (pin "2") (pinfunction "-_2") (pintype "passive"))
      (node (ref "L2") (pin "P$1") (pinfunction "P$1_P$1") (pintype "bidirectional"))
      (node (ref "U$5") (pin "SW") (pinfunction "SW_SW") (pintype "bidirectional"))
    )
    (net (code "30") (name "Net-(D3-PadA)") (class "Default")
      (node (ref "D3") (pin "A") (pinfunction "A_A") (pintype "passive"))
      (node (ref "R30") (pin "1") (pinfunction "1_1") (pintype "passive"))
    )
    (net (code "31") (name "Net-(D5-PadC)") (class "Default")
      (node (ref "D5") (pin "C") (pinfunction "C_C") (pintype "passive"))
      (node (ref "R31") (pin "1") (pinfunction "1_1") (pintype "passive"))
    )
    (net (code "32") (name "Net-(D6-PadA)") (class "Default")
      (node (ref "D6") (pin "A") (pinfunction "A_A") (pintype "passive"))
      (node (ref "R18") (pin "1") (pinfunction "1_1") (pintype "passive"))
    )
    (net (code "33") (name "Net-(L2-PadP$2)") (class "Default")
      (node (ref "L2") (pin "P$2") (pinfunction "P$2_P$2") (pintype "bidirectional"))
      (node (ref "R22") (pin "2") (pinfunction "2_2") (pintype "passive"))
      (node (ref "U$5") (pin "CSP") (pinfunction "CSP_CSP") (pintype "bidirectional"))
    )
    (net (code "34") (name "Net-(Q1-D)") (class "Default")
      (node (ref "Q1") (pin "3") (pinfunction "D_3") (pintype "passive"))
      (node (ref "U$7") (pin "NEG") (pinfunction "NEG_NEG") (pintype "bidirectional"))
    )
    (net (code "35") (name "Net-(Q2-D)") (class "Default")
      (node (ref "Q2") (pin "3") (pinfunction "D_3") (pintype "passive"))
      (node (ref "R8") (pin "2") (pinfunction "2_2") (pintype "passive"))
      (node (ref "R9") (pin "2") (pinfunction "2_2") (pintype "passive"))
    )
    (net (code "36") (name "Net-(Q3-D)") (class "Default")
      (node (ref "Q3") (pin "3") (pinfunction "D_3") (pintype "passive"))
      (node (ref "Q6") (pin "3") (pinfunction "G_3") (pintype "passive"))
      (node (ref "R34") (pin "1") (pinfunction "1_1") (pintype "passive"))
    )
    (net (code "37") (name "Net-(Q4-CATH)") (class "Default")
      (node (ref "Q4") (pin "CAT") (pinfunction "CATH_CAT") (pintype "bidirectional"))
      (node (ref "R8") (pin "1") (pinfunction "1_1") (pintype "passive"))
      (node (ref "TP16") (pin "1") (pinfunction "1_1") (pintype "passive"))
    )
    (net (code "38") (name "Net-(Q5-CATH)") (class "Default")
      (node (ref "Q5") (pin "CAT") (pinfunction "CATH_CAT") (pintype "bidirectional"))
      (node (ref "R9") (pin "1") (pinfunction "1_1") (pintype "passive"))
      (node (ref "TP17") (pin "1") (pinfunction "1_1") (pintype "passive"))
    )
    (net (code "39") (name "Net-(Q7-PadG)") (class "Default")
      (node (ref "Q7") (pin "G") (pinfunction "G_G") (pintype "bidirectional"))
      (node (ref "R23") (pin "1") (pinfunction "1_1") (pintype "passive"))
      (node (ref "R24") (pin "2") (pinfunction "2_2") (pintype "passive"))
      (node (ref "TP11") (pin "1") (pinfunction "1_1") (pintype "passive"))
    )
    (net (code "40") (name "Net-(R5-P$1)") (class "Default")
      (node (ref "JP4") (pin "1") (pinfunction "1_1") (pintype "passive"))
      (node (ref "R17") (pin "1") (pinfunction "1_1") (pintype "passive"))
      (node (ref "R5") (pin "P1") (pinfunction "P$1_P1") (pintype "bidirectional"))
      (node (ref "U$5") (pin "NTC") (pinfunction "NTC_NTC") (pintype "bidirectional"))
    )
    (net (code "41") (name "Net-(R20-Pad2)") (class "Default")
      (node (ref "R20") (pin "2") (pinfunction "2_2") (pintype "passive"))
      (node (ref "U$5") (pin "COMPV") (pinfunction "COMPV_COMPV") (pintype "bidirectional"))
    )
    (net (code "42") (name "Net-(R21-Pad2)") (class "Default")
      (node (ref "R21") (pin "2") (pinfunction "2_2") (pintype "passive"))
      (node (ref "U$5") (pin "COMPI") (pinfunction "COMPI_COMPI") (pintype "bidirectional"))
    )
    (net (code "43") (name "Net-(U$5-~{CHGOK})") (class "Default")
      (node (ref "D6") (pin "C") (pinfunction "C_C") (pintype "passive"))
      (node (ref "U$5") (pin "!CHGOK") (pinfunction "~{CHGOK}_!CHGOK") (pintype "bidirectional"))
    )
    (net (code "44") (name "Net-(U3-CAT)") (class "Default")
      (node (ref "R26") (pin "1") (pinfunction "1_1") (pintype "passive"))
      (node (ref "U3") (pin "CATH") (pinfunction "CAT_CATH") (pintype "bidirectional"))
    )
    (net (code "45") (name "Net-(U5-CAT)") (class "Default")
      (node (ref "R27") (pin "1") (pinfunction "1_1") (pintype "passive"))
      (node (ref "U5") (pin "CATH") (pinfunction "CAT_CATH") (pintype "bidirectional"))
    )
    (net (code "46") (name "Net-(U10-EN)") (class "Default")
      (node (ref "R1") (pin "1") (pinfunction "1_1") (pintype "passive"))
      (node (ref "TP29") (pin "1") (pinfunction "1_1") (pintype "passive"))
      (node (ref "U10") (pin "1") (pinfunction "PS/SYNC_1") (pintype "input"))
      (node (ref "U10") (pin "14") (pinfunction "EN_14") (pintype "input"))
    )
    (net (code "47") (name "Net-(U10-FB)") (class "Default")
      (node (ref "R2") (pin "1") (pinfunction "1_1") (pintype "passive"))
      (node (ref "R3") (pin "2") (pinfunction "2_2") (pintype "passive"))
      (node (ref "U10") (pin "5") (pinfunction "FB_5") (pintype "passive"))
    )
    (net (code "48") (name "Net-(U10-FB2)") (class "Default")
      (node (ref "TP27") (pin "1") (pinfunction "1_1") (pintype "passive"))
      (node (ref "U10") (pin "6") (pinfunction "FB2_6") (pintype "passive"))
    )
    (net (code "49") (name "Net-(U10-L1)") (class "Default")
      (node (ref "L1") (pin "P$1") (pinfunction "P$1_P$1") (pintype "bidirectional"))
      (node (ref "U10") (pin "11") (pinfunction "L1_11") (pintype "passive"))
    )
    (net (code "50") (name "Net-(U10-L2)") (class "Default")
      (node (ref "L1") (pin "P$2") (pinfunction "P$2_P$2") (pintype "bidirectional"))
      (node (ref "U10") (pin "9") (pinfunction "L2_9") (pintype "passive"))
    )
    (net (code "51") (name "Net-(U10-PG)") (class "Default")
      (node (ref "TP26") (pin "1") (pinfunction "1_1") (pintype "passive"))
      (node (ref "U10") (pin "2") (pinfunction "PG_2") (pintype "open_collector"))
    )
    (net (code "52") (name "Net-(U10-VAUX)") (class "Default")
      (node (ref "C7") (pin "1") (pinfunction "1_1") (pintype "passive"))
      (node (ref "U10") (pin "3") (pinfunction "VAUX_3") (pintype "output"))
    )
    (net (code "53") (name "Net-(U10-VSEL)") (class "Default")
      (node (ref "R4") (pin "2") (pinfunction "2_2") (pintype "passive"))
      (node (ref "TP28") (pin "1") (pinfunction "1_1") (pintype "passive"))
      (node (ref "U10") (pin "15") (pinfunction "VSEL_15") (pintype "input"))
    )
    (net (code "54") (name "OSC_IN") (class "Default")
      (node (ref "C3") (pin "1") (pinfunction "1_1") (pintype "passive"))
      (node (ref "U1") (pin "2") (pinfunction "PF0-OSC_IN_2") (pintype "bidirectional"))
      (node (ref "Y1") (pin "IN/OUT") (pinfunction "IN/OUT_IN/OUT") (pintype "passive"))
    )
    (net (code "55") (name "OSC_OUT") (class "Default")
      (node (ref "C4") (pin "1") (pinfunction "1_1") (pintype "passive"))
      (node (ref "U1") (pin "3") (pinfunction "PF1-OSC_OUT_3") (pintype "bidirectional"))
      (node (ref "Y1") (pin "OUT/IN") (pinfunction "OUT/IN_OUT/IN") (pintype "passive"))
    )
    (net (code "56") (name "ROTSENE1") (class "Default")
      (node (ref "Q4") (pin "E") (pinfunction "EMIT_E") (pintype "bidirectional"))
      (node (ref "R7") (pin "2") (pinfunction "2_2") (pintype "passive"))
      (node (ref "TP5") (pin "1") (pinfunction "1_1") (pintype "passive"))
      (node (ref "U1") (pin "28") (pinfunction "PB5_28") (pintype "bidirectional"))
    )
    (net (code "57") (name "ROTSENSE2") (class "Default")
      (node (ref "Q5") (pin "E") (pinfunction "EMIT_E") (pintype "bidirectional"))
      (node (ref "R10") (pin "2") (pinfunction "2_2") (pintype "passive"))
      (node (ref "TP7") (pin "1") (pinfunction "1_1") (pintype "passive"))
      (node (ref "U1") (pin "27") (pinfunction "PB4_27") (pintype "bidirectional"))
    )
    (net (code "58") (name "ROTSENSE_PWR") (class "Default")
      (node (ref "Q2") (pin "1") (pinfunction "G_1") (pintype "passive"))
      (node (ref "R36") (pin "1") (pinfunction "1_1") (pintype "passive"))
      (node (ref "U1") (pin "26") (pinfunction "PB3_26") (pintype "bidirectional"))
    )
    (net (code "59") (name "SPKR") (class "Default")
      (node (ref "Q1") (pin "1") (pinfunction "G_1") (pintype "passive"))
      (node (ref "R37") (pin "1") (pinfunction "1_1") (pintype "passive"))
      (node (ref "U1") (pin "31") (pinfunction "PB8-BOOT0_31") (pintype "bidirectional"))
    )
    (net (code "60") (name "SWCLK") (class "Default")
      (node (ref "CM1") (pin "4") (pinfunction "SWDCLK/TCK_4") (pintype "passive"))
      (node (ref "U1") (pin "24") (pinfunction "PA14-SWCLK_24") (pintype "bidirectional"))
    )
    (net (code "61") (name "SWDIO") (class "Default")
      (node (ref "CM1") (pin "2") (pinfunction "SWDIO/TMS_2") (pintype "passive"))
      (node (ref "U1") (pin "23") (pinfunction "PA13-SWDIO_23") (pintype "bidirectional"))
    )
    (net (code "62") (name "T_DROGUE") (class "Default")
      (node (ref "JP2") (pin "6") (pinfunction "6_6") (pintype "passive"))
      (node (ref "TP12") (pin "1") (pinfunction "1_1") (pintype "passive"))
      (node (ref "U5") (pin "ANOD") (pinfunction "ANOD_ANOD") (pintype "bidirectional"))
    )
    (net (code "63") (name "T_MAIN") (class "Default")
      (node (ref "JP2") (pin "5") (pinfunction "5_5") (pintype "passive"))
      (node (ref "TP13") (pin "1") (pinfunction "1_1") (pintype "passive"))
      (node (ref "U3") (pin "ANOD") (pinfunction "ANOD_ANOD") (pintype "bidirectional"))
    )
    (net (code "64") (name "T_VLIPO") (class "Default")
      (node (ref "JP2") (pin "7") (pinfunction "7_7") (pintype "passive"))
      (node (ref "R26") (pin "2") (pinfunction "2_2") (pintype "passive"))
      (node (ref "R27") (pin "2") (pinfunction "2_2") (pintype "passive"))
    )
    (net (code "65") (name "UMB_ON") (class "Default")
      (node (ref "D3") (pin "C") (pinfunction "C_C") (pintype "passive"))
      (node (ref "R19") (pin "1") (pinfunction "1_1") (pintype "passive"))
      (node (ref "U$5") (pin "!ACOK") (pinfunction "~{ACOK}_!ACOK") (pintype "bidirectional"))
      (node (ref "U1") (pin "30") (pinfunction "PB7_30") (pintype "bidirectional"))
    )
    (net (code "66") (name "USART2_RX") (class "Default")
      (node (ref "JP3") (pin "1") (pinfunction "1_1") (pintype "passive"))
      (node (ref "TP3") (pin "1") (pinfunction "1_1") (pintype "passive"))
      (node (ref "U1") (pin "25") (pinfunction "PA15_25") (pintype "bidirectional"))
    )
    (net (code "67") (name "USART2_TX") (class "Default")
      (node (ref "JP3") (pin "2") (pinfunction "2_2") (pintype "passive"))
      (node (ref "TP4") (pin "1") (pinfunction "1_1") (pintype "passive"))
      (node (ref "U1") (pin "8") (pinfunction "PA2_8") (pintype "bidirectional"))
    )
    (net (code "68") (name "VBAT") (class "Default")
      (node (ref "C17") (pin "1") (pinfunction "1_1") (pintype "passive"))
      (node (ref "JP1") (pin "1") (pinfunction "1_1") (pintype "passive"))
      (node (ref "JP1") (pin "2") (pinfunction "2_2") (pintype "passive"))
      (node (ref "Q7") (pin "S1") (pinfunction "S_S1") (pintype "bidirectional"))
      (node (ref "Q7") (pin "S2") (pinfunction "S_S2") (pintype "bidirectional"))
      (node (ref "Q7") (pin "S3") (pinfunction "S_S3") (pintype "bidirectional"))
      (node (ref "R15") (pin "2") (pinfunction "2_2") (pintype "passive"))
      (node (ref "R22") (pin "1") (pinfunction "1_1") (pintype "passive"))
      (node (ref "R25") (pin "2") (pinfunction "2_2") (pintype "passive"))
      (node (ref "U$5") (pin "BATT") (pinfunction "BATT_BATT") (pintype "bidirectional"))
    )
    (net (code "69") (name "VUMB") (class "Default")
      (node (ref "C11") (pin "1") (pinfunction "1_1") (pintype "passive"))
      (node (ref "D1") (pin "1") (pinfunction "+_1") (pintype "passive"))
      (node (ref "JP2") (pin "3") (pinfunction "3_3") (pintype "passive"))
      (node (ref "U$5") (pin "VCC") (pinfunction "VCC_VCC") (pintype "bidirectional"))
    )
    (net (code "70") (name "unconnected-(CM1-NC{slash}TDI-Pad8)") (class "Default")
      (node (ref "CM1") (pin "8") (pinfunction "NC/TDI_8") (pintype "passive"))
    )
    (net (code "71") (name "unconnected-(CM1-SWO{slash}TDO-Pad6)") (class "Default")
      (node (ref "CM1") (pin "6") (pinfunction "SWO/TDO_6") (pintype "passive"))
    )
    (net (code "72") (name "unconnected-(U1-PA10-Pad20)") (class "Default")
      (node (ref "U1") (pin "20") (pinfunction "PA10_20") (pintype "bidirectional"))
    )
    (net (code "73") (name "unconnected-(U1-PB6-Pad29)") (class "Default")
      (node (ref "U1") (pin "29") (pinfunction "PB6_29") (pintype "bidirectional"))
    )
  )
)
